# main_board.net
KiCad netlist of a schematic drawn in EAGLE
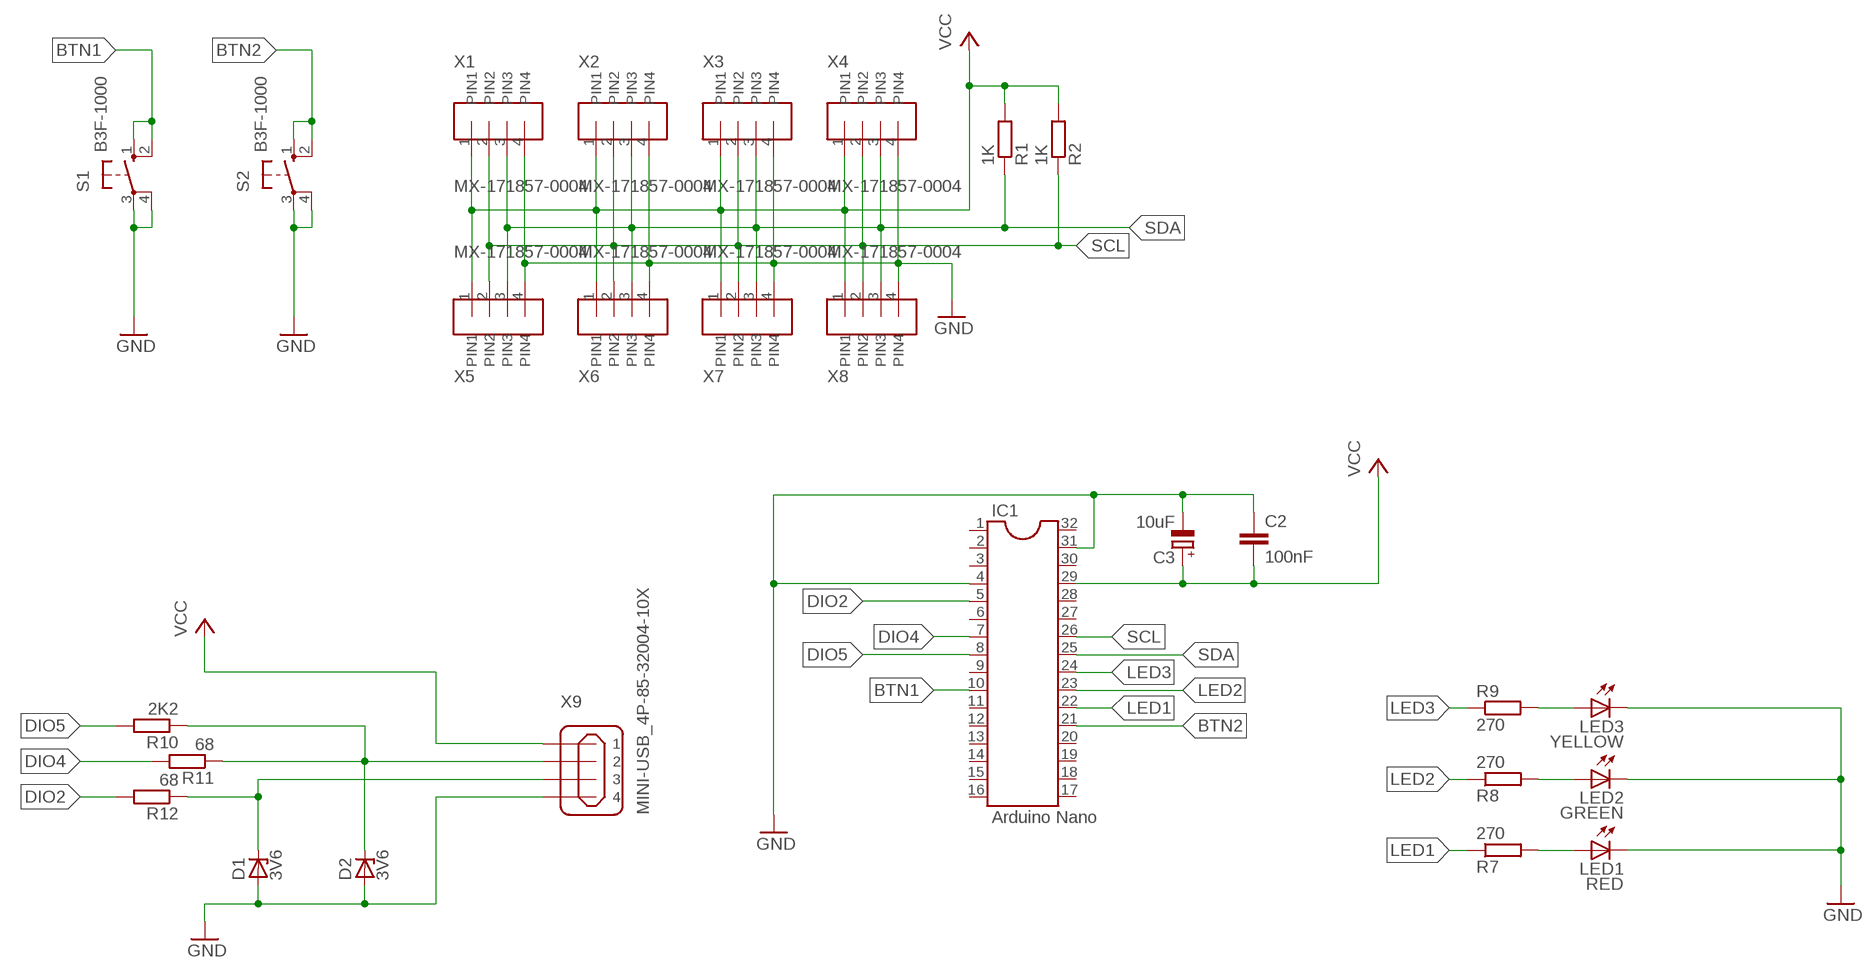
[diagram p0: schematic, sheet 1]

(export (version "E")
  (design (tool "Eeschema 10.0.6"))
  (components
    (comp (ref "C2")
      (value "100nF")
      (footprint "eagle-import:C050-030X075")
      (libsource (lib "eagle-import") (part "C-EU050-030X075"))
    )
    (comp (ref "C3")
      (value "10uF")
      (footprint "eagle-import:E2,5-7")
      (libsource (lib "eagle-import") (part "CPOL-EUE2.5-7"))
    )
    (comp (ref "D1")
      (value "3V6")
      (footprint "eagle-import:DO35Z10")
      (libsource (lib "eagle-import") (part "ZPD"))
    )
    (comp (ref "D2")
      (value "3V6")
      (footprint "eagle-import:DO35Z10")
      (libsource (lib "eagle-import") (part "ZPD"))
    )
    (comp (ref "IC1")
      (value "Arduino Nano")
      (footprint "eagle-import:DIL32")
      (libsource (lib "eagle-import") (part "DIL32"))
    )
    (comp (ref "LED1")
      (value "RED")
      (footprint "eagle-import:LED3MM")
      (fields (field (name "MF") "VISHAY SEMICONDUCTOR"))
      (libsource (lib "eagle-import") (part "TLLR4400"))
    )
    (comp (ref "LED2")
      (value "GREEN")
      (footprint "eagle-import:LED3MM")
      (fields (field (name "MF") "VISHAY SEMICONDUCTOR"))
      (libsource (lib "eagle-import") (part "TLLR4400"))
    )
    (comp (ref "LED3")
      (value "YELLOW")
      (footprint "eagle-import:LED3MM")
      (fields (field (name "MF") "VISHAY SEMICONDUCTOR"))
      (libsource (lib "eagle-import") (part "TLLR4400"))
    )
    (comp (ref "R1")
      (value "1K")
      (footprint "eagle-import:0204_7")
      (libsource (lib "eagle-import") (part "R-EU_0204/7"))
    )
    (comp (ref "R2")
      (value "1K")
      (footprint "eagle-import:0204_7")
      (libsource (lib "eagle-import") (part "R-EU_0204/7"))
    )
    (comp (ref "R7")
      (value "270")
      (footprint "eagle-import:0204_7")
      (libsource (lib "eagle-import") (part "R-EU_0204/7"))
    )
    (comp (ref "R8")
      (value "270")
      (footprint "eagle-import:0204_7")
      (libsource (lib "eagle-import") (part "R-EU_0204/7"))
    )
    (comp (ref "R9")
      (value "270")
      (footprint "eagle-import:0204_7")
      (libsource (lib "eagle-import") (part "R-EU_0204/7"))
    )
    (comp (ref "R10")
      (value "2K2")
      (footprint "eagle-import:0204_7")
      (libsource (lib "eagle-import") (part "R-EU_0204/7"))
    )
    (comp (ref "R11")
      (value "68")
      (footprint "eagle-import:0204_7")
      (libsource (lib "eagle-import") (part "R-EU_0204/7"))
    )
    (comp (ref "R12")
      (value "68")
      (footprint "eagle-import:0204_7")
      (libsource (lib "eagle-import") (part "R-EU_0204/7"))
    )
    (comp (ref "S1")
      (value "B3F-1000")
      (footprint "eagle-import:B3F-10XX")
      (libsource (lib "eagle-import") (part "10-XX"))
    )
    (comp (ref "S2")
      (value "B3F-1000")
      (footprint "eagle-import:B3F-10XX")
      (libsource (lib "eagle-import") (part "10-XX"))
    )
    (comp (ref "X1")
      (value "MX-171857-0004")
      (footprint "eagle-import:MX-171857-0004")
      (libsource (lib "eagle-import") (part "MX-171857-0004"))
    )
    (comp (ref "X2")
      (value "MX-171857-0004")
      (footprint "eagle-import:MX-171857-0004")
      (libsource (lib "eagle-import") (part "MX-171857-0004"))
    )
    (comp (ref "X3")
      (value "MX-171857-0004")
      (footprint "eagle-import:MX-171857-0004")
      (libsource (lib "eagle-import") (part "MX-171857-0004"))
    )
    (comp (ref "X4")
      (value "MX-171857-0004")
      (footprint "eagle-import:MX-171857-0004")
      (libsource (lib "eagle-import") (part "MX-171857-0004"))
    )
    (comp (ref "X5")
      (value "MX-171857-0004")
      (footprint "eagle-import:MX-171857-0004")
      (libsource (lib "eagle-import") (part "MX-171857-0004"))
    )
    (comp (ref "X6")
      (value "MX-171857-0004")
      (footprint "eagle-import:MX-171857-0004")
      (libsource (lib "eagle-import") (part "MX-171857-0004"))
    )
    (comp (ref "X7")
      (value "MX-171857-0004")
      (footprint "eagle-import:MX-171857-0004")
      (libsource (lib "eagle-import") (part "MX-171857-0004"))
    )
    (comp (ref "X8")
      (value "MX-171857-0004")
      (footprint "eagle-import:MX-171857-0004")
      (libsource (lib "eagle-import") (part "MX-171857-0004"))
    )
    (comp (ref "X9")
      (value "MINI-USB_4P-85-32004-10X")
      (footprint "eagle-import:85-32004-10X")
      (libsource (lib "eagle-import") (part "MINI-USB_4P-85-32004-10X"))
    )
  )
  (nets
    (net (code "1") (name "BTN1") (class "Default")
      (node (ref "IC1") (pin "10") (pinfunction "10_10") (pintype "passive"))
      (node (ref "S1") (pin "1") (pinfunction "S_1") (pintype "passive"))
      (node (ref "S1") (pin "2") (pinfunction "S1_2") (pintype "passive"))
    )
    (net (code "2") (name "BTN2") (class "Default")
      (node (ref "IC1") (pin "21") (pinfunction "21_21") (pintype "passive"))
      (node (ref "S2") (pin "1") (pinfunction "S_1") (pintype "passive"))
      (node (ref "S2") (pin "2") (pinfunction "S1_2") (pintype "passive"))
    )
    (net (code "3") (name "DIO2") (class "Default")
      (node (ref "IC1") (pin "5") (pinfunction "5_5") (pintype "passive"))
      (node (ref "R12") (pin "2") (pinfunction "2_2") (pintype "passive"))
    )
    (net (code "4") (name "DIO4") (class "Default")
      (node (ref "IC1") (pin "7") (pinfunction "7_7") (pintype "passive"))
      (node (ref "R11") (pin "2") (pinfunction "2_2") (pintype "passive"))
    )
    (net (code "5") (name "DIO5") (class "Default")
      (node (ref "IC1") (pin "8") (pinfunction "8_8") (pintype "passive"))
      (node (ref "R10") (pin "2") (pinfunction "2_2") (pintype "passive"))
    )
    (net (code "6") (name "GND") (class "Default")
      (node (ref "C2") (pin "1") (pinfunction "1_1") (pintype "passive"))
      (node (ref "C3") (pin "-") (pinfunction "-_-") (pintype "passive"))
      (node (ref "D1") (pin "A") (pinfunction "A_A") (pintype "passive"))
      (node (ref "D2") (pin "A") (pinfunction "A_A") (pintype "passive"))
      (node (ref "IC1") (pin "31") (pinfunction "31_31") (pintype "passive"))
      (node (ref "IC1") (pin "4") (pinfunction "4_4") (pintype "passive"))
      (node (ref "LED1") (pin "K") (pinfunction "C_K") (pintype "passive"))
      (node (ref "LED2") (pin "K") (pinfunction "C_K") (pintype "passive"))
      (node (ref "LED3") (pin "K") (pinfunction "C_K") (pintype "passive"))
      (node (ref "S1") (pin "3") (pinfunction "P_3") (pintype "passive"))
      (node (ref "S1") (pin "4") (pinfunction "P1_4") (pintype "passive"))
      (node (ref "S2") (pin "3") (pinfunction "P_3") (pintype "passive"))
      (node (ref "S2") (pin "4") (pinfunction "P1_4") (pintype "passive"))
      (node (ref "X1") (pin "4") (pinfunction "PIN4_4") (pintype "bidirectional"))
      (node (ref "X2") (pin "4") (pinfunction "PIN4_4") (pintype "bidirectional"))
      (node (ref "X3") (pin "4") (pinfunction "PIN4_4") (pintype "bidirectional"))
      (node (ref "X4") (pin "4") (pinfunction "PIN4_4") (pintype "bidirectional"))
      (node (ref "X5") (pin "4") (pinfunction "PIN4_4") (pintype "bidirectional"))
      (node (ref "X6") (pin "4") (pinfunction "PIN4_4") (pintype "bidirectional"))
      (node (ref "X7") (pin "4") (pinfunction "PIN4_4") (pintype "bidirectional"))
      (node (ref "X8") (pin "4") (pinfunction "PIN4_4") (pintype "bidirectional"))
      (node (ref "X9") (pin "4") (pinfunction "4_4") (pintype "passive"))
    )
    (net (code "7") (name "LED1") (class "Default")
      (node (ref "IC1") (pin "22") (pinfunction "22_22") (pintype "passive"))
      (node (ref "R7") (pin "1") (pinfunction "1_1") (pintype "passive"))
    )
    (net (code "8") (name "LED2") (class "Default")
      (node (ref "IC1") (pin "23") (pinfunction "23_23") (pintype "passive"))
      (node (ref "R8") (pin "1") (pinfunction "1_1") (pintype "passive"))
    )
    (net (code "9") (name "LED3") (class "Default")
      (node (ref "IC1") (pin "24") (pinfunction "24_24") (pintype "passive"))
      (node (ref "R9") (pin "1") (pinfunction "1_1") (pintype "passive"))
    )
    (net (code "10") (name "Net-(D1-PadC)") (class "Default")
      (node (ref "D1") (pin "C") (pinfunction "C_C") (pintype "passive"))
      (node (ref "R12") (pin "1") (pinfunction "1_1") (pintype "passive"))
      (node (ref "X9") (pin "3") (pinfunction "3_3") (pintype "passive"))
    )
    (net (code "11") (name "Net-(D2-PadC)") (class "Default")
      (node (ref "D2") (pin "C") (pinfunction "C_C") (pintype "passive"))
      (node (ref "R10") (pin "1") (pinfunction "1_1") (pintype "passive"))
      (node (ref "R11") (pin "1") (pinfunction "1_1") (pintype "passive"))
      (node (ref "X9") (pin "2") (pinfunction "2_2") (pintype "passive"))
    )
    (net (code "12") (name "Net-(LED1-PadA)") (class "Default")
      (node (ref "LED1") (pin "A") (pinfunction "A_A") (pintype "passive"))
      (node (ref "R7") (pin "2") (pinfunction "2_2") (pintype "passive"))
    )
    (net (code "13") (name "Net-(LED2-PadA)") (class "Default")
      (node (ref "LED2") (pin "A") (pinfunction "A_A") (pintype "passive"))
      (node (ref "R8") (pin "2") (pinfunction "2_2") (pintype "passive"))
    )
    (net (code "14") (name "Net-(LED3-PadA)") (class "Default")
      (node (ref "LED3") (pin "A") (pinfunction "A_A") (pintype "passive"))
      (node (ref "R9") (pin "2") (pinfunction "2_2") (pintype "passive"))
    )
    (net (code "15") (name "SCL") (class "Default")
      (node (ref "IC1") (pin "26") (pinfunction "26_26") (pintype "passive"))
      (node (ref "R2") (pin "1") (pinfunction "1_1") (pintype "passive"))
      (node (ref "X1") (pin "2") (pinfunction "PIN2_2") (pintype "bidirectional"))
      (node (ref "X2") (pin "2") (pinfunction "PIN2_2") (pintype "bidirectional"))
      (node (ref "X3") (pin "2") (pinfunction "PIN2_2") (pintype "bidirectional"))
      (node (ref "X4") (pin "2") (pinfunction "PIN2_2") (pintype "bidirectional"))
      (node (ref "X5") (pin "2") (pinfunction "PIN2_2") (pintype "bidirectional"))
      (node (ref "X6") (pin "2") (pinfunction "PIN2_2") (pintype "bidirectional"))
      (node (ref "X7") (pin "2") (pinfunction "PIN2_2") (pintype "bidirectional"))
      (node (ref "X8") (pin "2") (pinfunction "PIN2_2") (pintype "bidirectional"))
    )
    (net (code "16") (name "SDA") (class "Default")
      (node (ref "IC1") (pin "25") (pinfunction "25_25") (pintype "passive"))
      (node (ref "R1") (pin "1") (pinfunction "1_1") (pintype "passive"))
      (node (ref "X1") (pin "3") (pinfunction "PIN3_3") (pintype "bidirectional"))
      (node (ref "X2") (pin "3") (pinfunction "PIN3_3") (pintype "bidirectional"))
      (node (ref "X3") (pin "3") (pinfunction "PIN3_3") (pintype "bidirectional"))
      (node (ref "X4") (pin "3") (pinfunction "PIN3_3") (pintype "bidirectional"))
      (node (ref "X5") (pin "3") (pinfunction "PIN3_3") (pintype "bidirectional"))
      (node (ref "X6") (pin "3") (pinfunction "PIN3_3") (pintype "bidirectional"))
      (node (ref "X7") (pin "3") (pinfunction "PIN3_3") (pintype "bidirectional"))
      (node (ref "X8") (pin "3") (pinfunction "PIN3_3") (pintype "bidirectional"))
    )
    (net (code "17") (name "VCC") (class "Default")
      (node (ref "C2") (pin "2") (pinfunction "2_2") (pintype "passive"))
      (node (ref "C3") (pin "+") (pinfunction "+_+") (pintype "passive"))
      (node (ref "IC1") (pin "29") (pinfunction "29_29") (pintype "passive"))
      (node (ref "R1") (pin "2") (pinfunction "2_2") (pintype "passive"))
      (node (ref "R2") (pin "2") (pinfunction "2_2") (pintype "passive"))
      (node (ref "X1") (pin "1") (pinfunction "PIN1_1") (pintype "bidirectional"))
      (node (ref "X2") (pin "1") (pinfunction "PIN1_1") (pintype "bidirectional"))
      (node (ref "X3") (pin "1") (pinfunction "PIN1_1") (pintype "bidirectional"))
      (node (ref "X4") (pin "1") (pinfunction "PIN1_1") (pintype "bidirectional"))
      (node (ref "X5") (pin "1") (pinfunction "PIN1_1") (pintype "bidirectional"))
      (node (ref "X6") (pin "1") (pinfunction "PIN1_1") (pintype "bidirectional"))
      (node (ref "X7") (pin "1") (pinfunction "PIN1_1") (pintype "bidirectional"))
      (node (ref "X8") (pin "1") (pinfunction "PIN1_1") (pintype "bidirectional"))
      (node (ref "X9") (pin "1") (pinfunction "1_1") (pintype "passive"))
    )
    (net (code "18") (name "unconnected-(IC1-Pad1)") (class "Default")
      (node (ref "IC1") (pin "1") (pinfunction "1_1") (pintype "passive"))
    )
    (net (code "19") (name "unconnected-(IC1-Pad2)") (class "Default")
      (node (ref "IC1") (pin "2") (pinfunction "2_2") (pintype "passive"))
    )
    (net (code "20") (name "unconnected-(IC1-Pad3)") (class "Default")
      (node (ref "IC1") (pin "3") (pinfunction "3_3") (pintype "passive"))
    )
    (net (code "21") (name "unconnected-(IC1-Pad6)") (class "Default")
      (node (ref "IC1") (pin "6") (pinfunction "6_6") (pintype "passive"))
    )
    (net (code "22") (name "unconnected-(IC1-Pad9)") (class "Default")
      (node (ref "IC1") (pin "9") (pinfunction "9_9") (pintype "passive"))
    )
    (net (code "23") (name "unconnected-(IC1-Pad11)") (class "Default")
      (node (ref "IC1") (pin "11") (pinfunction "11_11") (pintype "passive"))
    )
    (net (code "24") (name "unconnected-(IC1-Pad12)") (class "Default")
      (node (ref "IC1") (pin "12") (pinfunction "12_12") (pintype "passive"))
    )
    (net (code "25") (name "unconnected-(IC1-Pad13)") (class "Default")
      (node (ref "IC1") (pin "13") (pinfunction "13_13") (pintype "passive"))
    )
    (net (code "26") (name "unconnected-(IC1-Pad14)") (class "Default")
      (node (ref "IC1") (pin "14") (pinfunction "14_14") (pintype "passive"))
    )
    (net (code "27") (name "unconnected-(IC1-Pad15)") (class "Default")
      (node (ref "IC1") (pin "15") (pinfunction "15_15") (pintype "passive"))
    )
    (net (code "28") (name "unconnected-(IC1-Pad16)") (class "Default")
      (node (ref "IC1") (pin "16") (pinfunction "16_16") (pintype "passive"))
    )
    (net (code "29") (name "unconnected-(IC1-Pad17)") (class "Default")
      (node (ref "IC1") (pin "17") (pinfunction "17_17") (pintype "passive"))
    )
    (net (code "30") (name "unconnected-(IC1-Pad18)") (class "Default")
      (node (ref "IC1") (pin "18") (pinfunction "18_18") (pintype "passive"))
    )
    (net (code "31") (name "unconnected-(IC1-Pad19)") (class "Default")
      (node (ref "IC1") (pin "19") (pinfunction "19_19") (pintype "passive"))
    )
    (net (code "32") (name "unconnected-(IC1-Pad20)") (class "Default")
      (node (ref "IC1") (pin "20") (pinfunction "20_20") (pintype "passive"))
    )
    (net (code "33") (name "unconnected-(IC1-Pad27)") (class "Default")
      (node (ref "IC1") (pin "27") (pinfunction "27_27") (pintype "passive"))
    )
    (net (code "34") (name "unconnected-(IC1-Pad28)") (class "Default")
      (node (ref "IC1") (pin "28") (pinfunction "28_28") (pintype "passive"))
    )
    (net (code "35") (name "unconnected-(IC1-Pad30)") (class "Default")
      (node (ref "IC1") (pin "30") (pinfunction "30_30") (pintype "passive"))
    )
    (net (code "36") (name "unconnected-(IC1-Pad32)") (class "Default")
      (node (ref "IC1") (pin "32") (pinfunction "32_32") (pintype "passive"))
    )
  )
)
